# PSU_LM317_9V0.net
KiCad netlist of a schematic drawn in Altium Designer
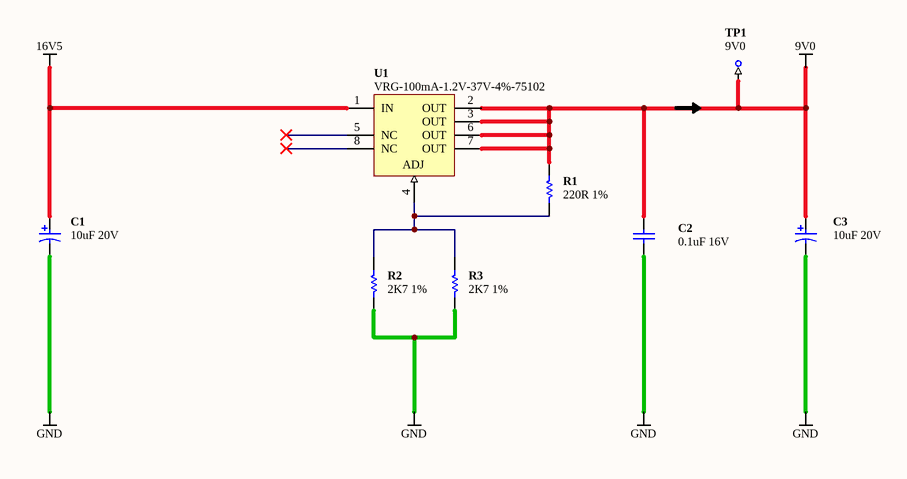
[diagram p0: PSU_LM317_9V0.SchDoc]

(export (version "E")
  (design (tool "Eeschema 10.0.6"))
  (components
    (comp (ref "C1")
      (value "10uF 20V")
      (footprint "CAPC3528-STAR")
      (description "Capacitor, Tantalum, 10uF 10% 20V MCCT-B (3528)")
      (fields (field (name "TOLERANCE") "10 %"))
      (libsource (lib "altium-import") (part "root_0_CAP-P_"))
    )
    (comp (ref "C2")
      (value "0.1uF 16V")
      (footprint "CAPC1005-STAR")
      (description "Capacitor, Ceramic, 0.1uF 10% 16V 0402 (1005) X7R")
      (fields (field (name "TOLERANCE") "10 %"))
      (libsource (lib "altium-import") (part "root_0_CAP-NP_"))
    )
    (comp (ref "C3")
      (value "10uF 20V")
      (footprint "CAPC3528-STAR")
      (description "Capacitor, Tantalum, 10uF 10% 20V MCCT-B (3528)")
      (fields (field (name "TOLERANCE") "10 %"))
      (libsource (lib "altium-import") (part "root_0_CAP-P_"))
    )
    (comp (ref "R1")
      (value "220R 1%")
      (footprint "RESC1005-STAR")
      (description "Resistor, 220R 1% 0402 (1005)")
      (fields (field (name "TOLERANCE") "1 %"))
      (libsource (lib "altium-import") (part "root_2_mirrored_RES_"))
    )
    (comp (ref "R2")
      (value "2K7 1%")
      (footprint "RESC1005-STAR")
      (description "Resistor, 2K7 1% 0402 (1005)")
      (fields (field (name "TOLERANCE") "1 %"))
      (libsource (lib "altium-import") (part "root_2_mirrored_RES_"))
    )
    (comp (ref "R3")
      (value "2K7 1%")
      (footprint "RESC1005-STAR")
      (description "Resistor, 2K7 1% 0402 (1005)")
      (fields (field (name "TOLERANCE") "1 %"))
      (libsource (lib "altium-import") (part "root_2_mirrored_RES_"))
    )
    (comp (ref "TP1")
      (value "9V0")
      (footprint "TestPin")
      (description "Test Point, PCB Mount with Silkscreen Box")
      (libsource (lib "AltiumDesignLibrary") (part "TestPin"))
    )
    (comp (ref "U1")
      (value "VRG-100mA-1.2V-37V-4%-75102")
      (footprint "SOP127P600-8")
      (description "LM317LDR2, 3-Terminal Adjustable Regulator")
      (libsource (lib "altium-import") (part "root_0_VRG-ADJ-8_"))
    )
  )
  (nets
    (net (code "1") (name "9V0") (class "Default")
      (node (ref "C2") (pin "1") (pinfunction "1_1") (pintype "passive"))
      (node (ref "C3") (pin "1") (pinfunction "1_1") (pintype "passive"))
      (node (ref "R1") (pin "2") (pinfunction "2_2") (pintype "passive"))
      (node (ref "TP1") (pin "1") (pinfunction "1_1") (pintype "input"))
      (node (ref "U1") (pin "2") (pinfunction "OUT_2") (pintype "power_in"))
      (node (ref "U1") (pin "3") (pinfunction "OUT_3") (pintype "power_in"))
      (node (ref "U1") (pin "6") (pinfunction "OUT_6") (pintype "power_in"))
      (node (ref "U1") (pin "7") (pinfunction "OUT_7") (pintype "power_in"))
    )
    (net (code "2") (name "16V5") (class "Default")
      (node (ref "C1") (pin "1") (pinfunction "1_1") (pintype "passive"))
      (node (ref "U1") (pin "1") (pinfunction "IN_1") (pintype "power_in"))
    )
    (net (code "3") (name "GND") (class "Default")
      (node (ref "C1") (pin "2") (pinfunction "2_2") (pintype "passive"))
      (node (ref "C2") (pin "2") (pinfunction "2_2") (pintype "passive"))
      (node (ref "C3") (pin "2") (pinfunction "2_2") (pintype "passive"))
      (node (ref "R2") (pin "1") (pinfunction "1_1") (pintype "passive"))
      (node (ref "R3") (pin "1") (pinfunction "1_1") (pintype "passive"))
    )
    (net (code "4") (name "Net-(U1-ADJ)") (class "Default")
      (node (ref "R1") (pin "1") (pinfunction "1_1") (pintype "passive"))
      (node (ref "R2") (pin "2") (pinfunction "2_2") (pintype "passive"))
      (node (ref "R3") (pin "2") (pinfunction "2_2") (pintype "passive"))
      (node (ref "U1") (pin "4") (pinfunction "ADJ_4") (pintype "input"))
    )
    (net (code "5") (name "unconnected-(U1-NC-Pad5)") (class "Default")
      (node (ref "U1") (pin "5") (pinfunction "NC_5") (pintype "passive+no_connect"))
    )
    (net (code "6") (name "unconnected-(U1-NC-Pad8)") (class "Default")
      (node (ref "U1") (pin "8") (pinfunction "NC_8") (pintype "passive+no_connect"))
    )
  )
)
